# attiny_pogo_pgm.net
KiCad netlist of a schematic drawn in EAGLE
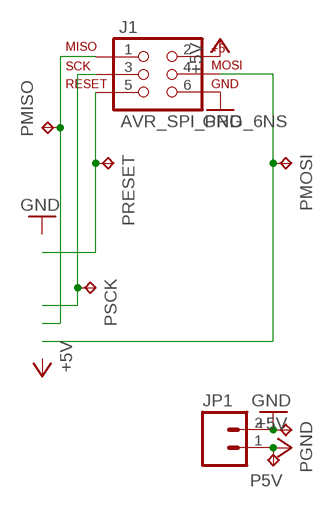
[diagram p0: schematic, sheet 1]

(export (version "E")
  (design (tool "Eeschema 10.0.6"))
  (components
    (comp (ref "J1")
      (value "AVR_SPI_PRG_6NS")
      (footprint "eagle-import:2X3-NS")
      (libsource (lib "eagle-import") (part "AVR_SPI_PRG_6NS"))
    )
    (comp (ref "JP1")
      (value "M02PTH")
      (footprint "eagle-import:1X02")
      (libsource (lib "eagle-import") (part "M02PTH"))
    )
    (comp (ref "P5V")
      (value "TPTP10R")
      (footprint "eagle-import:TP10R")
      (libsource (lib "eagle-import") (part "TPTP10R"))
    )
    (comp (ref "PGND")
      (value "TPTP10R")
      (footprint "eagle-import:TP10R")
      (libsource (lib "eagle-import") (part "TPTP10R"))
    )
    (comp (ref "PMISO")
      (value "TPTP10R")
      (footprint "eagle-import:TP10R")
      (libsource (lib "eagle-import") (part "TPTP10R"))
    )
    (comp (ref "PMOSI")
      (value "TPTP10R")
      (footprint "eagle-import:TP10R")
      (libsource (lib "eagle-import") (part "TPTP10R"))
    )
    (comp (ref "PRESET")
      (value "TPTP10R")
      (footprint "eagle-import:TP10R")
      (libsource (lib "eagle-import") (part "TPTP10R"))
    )
    (comp (ref "PSCK")
      (value "TPTP10R")
      (footprint "eagle-import:TP10R")
      (libsource (lib "eagle-import") (part "TPTP10R"))
    )
  )
  (nets
    (net (code "1") (name "+5V") (class "Default")
      (node (ref "J1") (pin "2") (pinfunction "2_2") (pintype "passive"))
      (node (ref "JP1") (pin "1") (pinfunction "1_1") (pintype "passive"))
      (node (ref "P5V") (pin "TP") (pinfunction "TP_TP") (pintype "input"))
    )
    (net (code "2") (name "GND") (class "Default")
      (node (ref "J1") (pin "6") (pinfunction "6_6") (pintype "passive"))
      (node (ref "JP1") (pin "2") (pinfunction "2_2") (pintype "passive"))
      (node (ref "PGND") (pin "TP") (pinfunction "TP_TP") (pintype "input"))
    )
    (net (code "3") (name "Net-(J1-Pad1)") (class "Default")
      (node (ref "J1") (pin "1") (pinfunction "1_1") (pintype "passive"))
      (node (ref "PMISO") (pin "TP") (pinfunction "TP_TP") (pintype "input"))
    )
    (net (code "4") (name "Net-(J1-Pad3)") (class "Default")
      (node (ref "J1") (pin "3") (pinfunction "3_3") (pintype "passive"))
      (node (ref "PSCK") (pin "TP") (pinfunction "TP_TP") (pintype "input"))
    )
    (net (code "5") (name "Net-(J1-Pad4)") (class "Default")
      (node (ref "J1") (pin "4") (pinfunction "4_4") (pintype "passive"))
      (node (ref "PMOSI") (pin "TP") (pinfunction "TP_TP") (pintype "input"))
    )
    (net (code "6") (name "Net-(J1-Pad5)") (class "Default")
      (node (ref "J1") (pin "5") (pinfunction "5_5") (pintype "passive"))
      (node (ref "PRESET") (pin "TP") (pinfunction "TP_TP") (pintype "input"))
    )
  )
)
